# Sheet1.net
KiCad netlist of a schematic drawn in Altium Designer
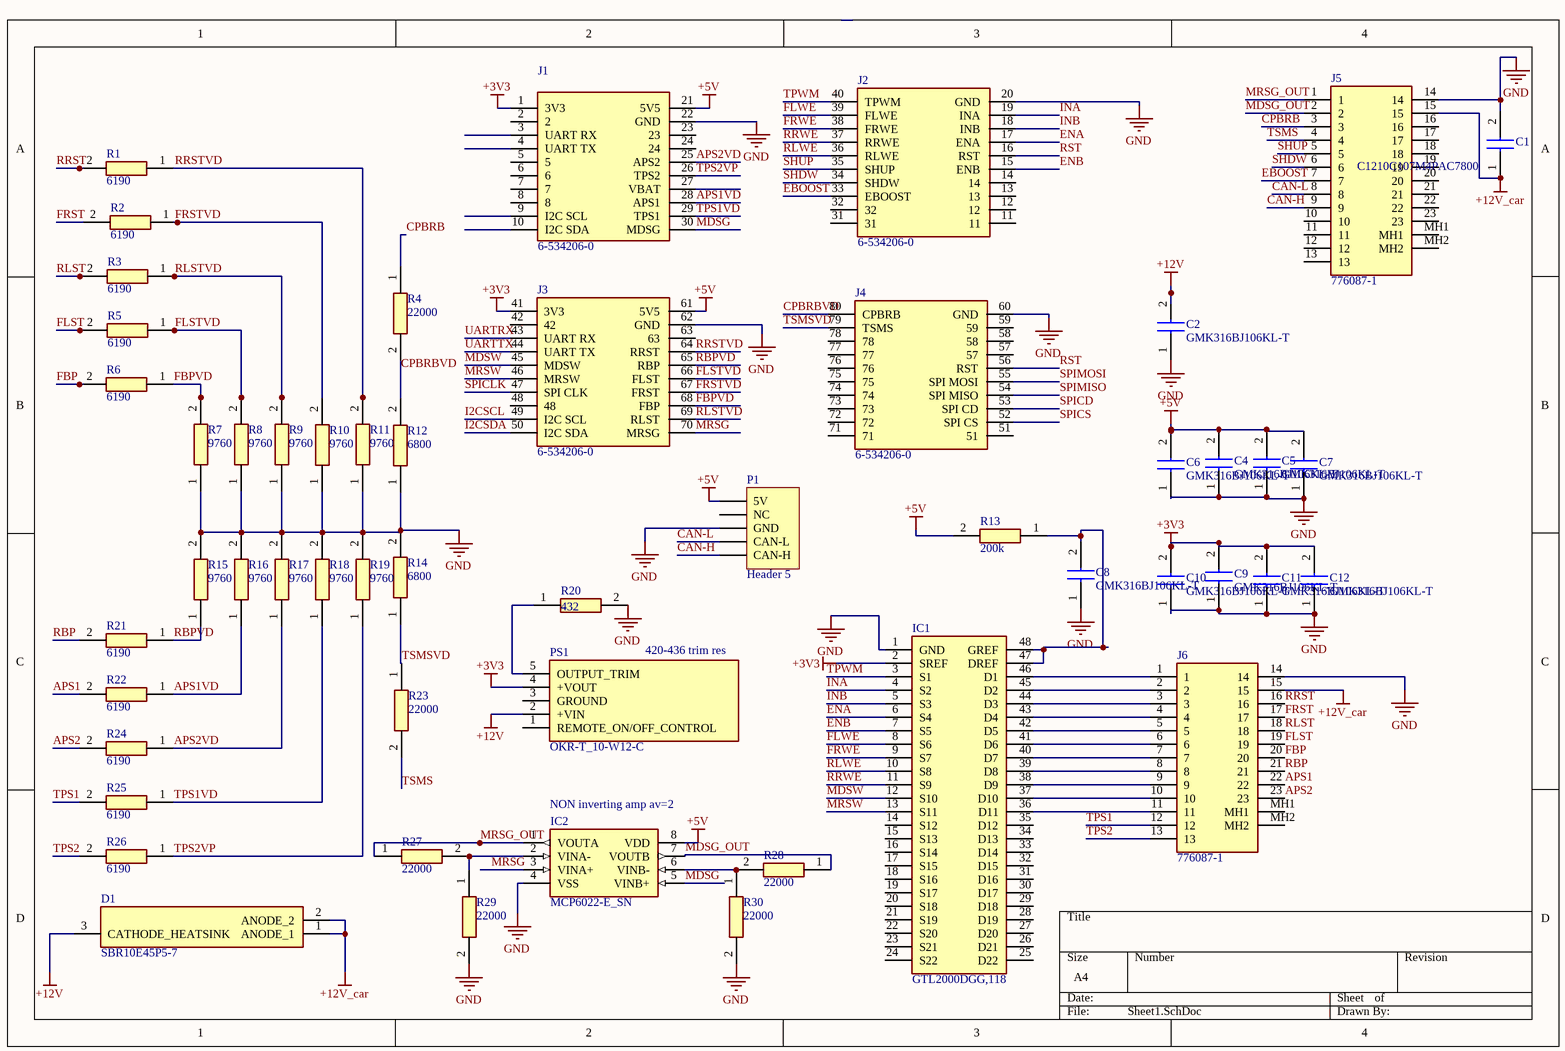
[diagram p0: Sheet1.SchDoc]

(export (version "E")
  (design (tool "Eeschema 10.0.6"))
  (components
    (comp (ref "C1")
      (value "C1210C107M4PAC7800")
      (footprint "SamacSys:CAPC3225X280N")
      (description "Capacitor")
      (libsource (lib "*") (part "C1210C107M4PAC7800"))
    )
    (comp (ref "C2")
      (value "GMK316BJ106KL-T")
      (footprint "SamacSys:CAPC3216X190N")
      (description "Capacitor")
      (fields (field (name "MOUSER PART NUMBER") "963-GMK316BJ106KL-T"))
      (libsource (lib "*") (part "GMK316BJ106KL-T"))
    )
    (comp (ref "C4")
      (value "GMK316BJ106KL-T")
      (footprint "SamacSys:CAPC3216X190N")
      (description "Capacitor")
      (fields (field (name "MOUSER PART NUMBER") "963-GMK316BJ106KL-T"))
      (libsource (lib "*") (part "GMK316BJ106KL-T"))
    )
    (comp (ref "C5")
      (value "GMK316BJ106KL-T")
      (footprint "SamacSys:CAPC3216X190N")
      (description "Capacitor")
      (fields (field (name "MOUSER PART NUMBER") "963-GMK316BJ106KL-T"))
      (libsource (lib "*") (part "GMK316BJ106KL-T"))
    )
    (comp (ref "C6")
      (value "GMK316BJ106KL-T")
      (footprint "SamacSys:CAPC3216X190N")
      (description "Capacitor")
      (fields (field (name "MOUSER PART NUMBER") "963-GMK316BJ106KL-T"))
      (libsource (lib "*") (part "GMK316BJ106KL-T"))
    )
    (comp (ref "C7")
      (value "GMK316BJ106KL-T")
      (footprint "SamacSys:CAPC3216X190N")
      (description "Capacitor")
      (fields (field (name "MOUSER PART NUMBER") "963-GMK316BJ106KL-T"))
      (libsource (lib "*") (part "GMK316BJ106KL-T"))
    )
    (comp (ref "C8")
      (value "GMK316BJ106KL-T")
      (footprint "SamacSys:CAPC3216X190N")
      (description "Capacitor")
      (fields (field (name "MOUSER PART NUMBER") "963-GMK316BJ106KL-T"))
      (libsource (lib "*") (part "GMK316BJ106KL-T"))
    )
    (comp (ref "C9")
      (value "GMK316BJ106KL-T")
      (footprint "SamacSys:CAPC3216X190N")
      (description "Capacitor")
      (fields (field (name "MOUSER PART NUMBER") "963-GMK316BJ106KL-T"))
      (libsource (lib "*") (part "GMK316BJ106KL-T"))
    )
    (comp (ref "C10")
      (value "GMK316BJ106KL-T")
      (footprint "SamacSys:CAPC3216X190N")
      (description "Capacitor")
      (fields (field (name "MOUSER PART NUMBER") "963-GMK316BJ106KL-T"))
      (libsource (lib "*") (part "GMK316BJ106KL-T"))
    )
    (comp (ref "C11")
      (value "GMK316BJ106KL-T")
      (footprint "SamacSys:CAPC3216X190N")
      (description "Capacitor")
      (fields (field (name "MOUSER PART NUMBER") "963-GMK316BJ106KL-T"))
      (libsource (lib "*") (part "GMK316BJ106KL-T"))
    )
    (comp (ref "C12")
      (value "GMK316BJ106KL-T")
      (footprint "SamacSys:CAPC3216X190N")
      (description "Capacitor")
      (fields (field (name "MOUSER PART NUMBER") "963-GMK316BJ106KL-T"))
      (libsource (lib "*") (part "GMK316BJ106KL-T"))
    )
    (comp (ref "D1")
      (value "SBR10E45P5-7")
      (footprint "SamacSys:POWERDI5")
      (description "Schottky Diode")
      (fields (field (name "MOUSER PART NUMBER") "621-SBR10E45P5-7"))
      (libsource (lib "*") (part "SBR10E45P5-7"))
    )
    (comp (ref "IC1")
      (value "GTL2000DGG,118")
      (footprint "SamacSys:SOP50P810X120-48N")
      (description "Integrated Circuit")
      (fields (field (name "MOUSER PART NUMBER") "771-GTL2000DGG118"))
      (libsource (lib "*") (part "GTL2000DGG,118"))
    )
    (comp (ref "IC2")
      (value "MCP6022-E_SN")
      (footprint "SamacSys:SOIC127P600X175-8N")
      (description "Integrated Circuit")
      (fields
        (field (name "MANUFACTURER_PART_NUMBER") "MCP6022-E/SN")
        (field (name "MOUSER PART NUMBER") "579-MCP6022-E/SN")
      )
      (libsource (lib "TiSupervisoryController") (part "MCP6022-E_SN"))
    )
    (comp (ref "J1")
      (value "6-534206-0")
      (footprint "206-0")
      (description "Connector")
      (fields (field (name "MOUSER PART NUMBER") "571-6-534206-0") (field (name "RS PART NUMBER") "6803445P"))
      (libsource (lib "TiSupervisoryController") (part "6-534206-0"))
    )
    (comp (ref "J2")
      (value "6-534206-0")
      (footprint "206-0_1")
      (description "Connector")
      (fields (field (name "MOUSER PART NUMBER") "571-6-534206-0") (field (name "RS PART NUMBER") "6803445P"))
      (libsource (lib "TiSupervisoryController") (part "6-534206-0_1"))
    )
    (comp (ref "J3")
      (value "6-534206-0")
      (footprint "206-0_2")
      (description "Connector")
      (fields (field (name "MOUSER PART NUMBER") "571-6-534206-0") (field (name "RS PART NUMBER") "6803445P"))
      (libsource (lib "TiSupervisoryController") (part "6-534206-0_2"))
    )
    (comp (ref "J4")
      (value "6-534206-0")
      (footprint "206-0_3")
      (description "Connector")
      (fields (field (name "MOUSER PART NUMBER") "571-6-534206-0") (field (name "RS PART NUMBER") "6803445P"))
      (libsource (lib "TiSupervisoryController") (part "6-534206-0_3"))
    )
    (comp (ref "J5")
      (value "776087-1")
      (footprint "PCB1:7760871")
      (description "Connector")
      (fields (field (name "MOUSER PART NUMBER") "571-776087-1") (field (name "RS PART NUMBER") "7181471P"))
      (libsource (lib "*") (part "776087-1"))
    )
    (comp (ref "J6")
      (value "776087-1")
      (footprint "PCB1:7760871")
      (description "Connector")
      (fields (field (name "MOUSER PART NUMBER") "571-776087-1") (field (name "RS PART NUMBER") "7181471P"))
      (libsource (lib "*") (part "776087-1"))
    )
    (comp (ref "P1")
      (value "Header 5")
      (footprint "HDR1X5")
      (description "Header, 5-Pin")
      (fields (field (name "PUBLISHER") "Altium Limited"))
      (libsource (lib "TiSupervisoryController") (part "Header 5"))
    )
    (comp (ref "PS1")
      (value "OKR-T_10-W12-C")
      (footprint "SamacSys:OKRT10W12C")
      (description "Power Supply")
      (fields
        (field (name "MANUFACTURER_PART_NUMBER") "OKR-T/10-W12-C")
        (field (name "MOUSER PART NUMBER") "580-OKR-T/10-W12-C")
      )
      (libsource (lib "*") (part "OKR-T_10-W12-C"))
    )
    (comp (ref "R1")
      (value "6190")
      (footprint "SamacSys:RESC3116X70N")
      (description "Resistor")
      (fields
        (field (name "MANUFACTURER_PART_NUMBER") "ERJ-8ENF6191V")
        (field (name "MOUSER PART NUMBER") "667-ERJ-8ENF6191V")
      )
      (libsource (lib "*") (part "ERJ-8ENF1000V"))
    )
    (comp (ref "R2")
      (value "6190")
      (footprint "SamacSys:RESC3116X70N")
      (description "Resistor")
      (fields
        (field (name "MANUFACTURER_PART_NUMBER") "ERJ-8ENF6191V")
        (field (name "MOUSER PART NUMBER") "667-ERJ-8ENF6191V")
      )
      (libsource (lib "*") (part "ERJ-8ENF1000V"))
    )
    (comp (ref "R3")
      (value "6190")
      (footprint "SamacSys:RESC3116X70N")
      (description "Resistor")
      (fields
        (field (name "MANUFACTURER_PART_NUMBER") "ERJ-8ENF6191V")
        (field (name "MOUSER PART NUMBER") "667-ERJ-8ENF6191V")
      )
      (libsource (lib "*") (part "ERJ-8ENF1000V"))
    )
    (comp (ref "R4")
      (value "22000")
      (footprint "SamacSys:RESC3116X70N")
      (description "Resistor")
      (fields
        (field (name "MANUFACTURER_PART_NUMBER") "ERJ-8ENF2201V")
        (field (name "MOUSER PART NUMBER") "667-ERJ-8ENF2201V")
      )
      (libsource (lib "") (part "ERJ-8ENF1000V_3"))
    )
    (comp (ref "R5")
      (value "6190")
      (footprint "SamacSys:RESC3116X70N")
      (description "Resistor")
      (fields
        (field (name "MANUFACTURER_PART_NUMBER") "ERJ-8ENF6191V")
        (field (name "MOUSER PART NUMBER") "667-ERJ-8ENF6191V")
      )
      (libsource (lib "*") (part "ERJ-8ENF1000V"))
    )
    (comp (ref "R6")
      (value "6190")
      (footprint "SamacSys:RESC3116X70N")
      (description "Resistor")
      (fields
        (field (name "MANUFACTURER_PART_NUMBER") "ERJ-8ENF6191V")
        (field (name "MOUSER PART NUMBER") "667-ERJ-8ENF6191V")
      )
      (libsource (lib "*") (part "ERJ-8ENF1000V"))
    )
    (comp (ref "R7")
      (value "9760")
      (footprint "SamacSys:RESC3116X70N")
      (description "Resistor")
      (fields
        (field (name "MANUFACTURER_PART_NUMBER") "ERJ-8ENF9761V")
        (field (name "MOUSER PART NUMBER") "667-ERJ-8ENF9761V")
      )
      (libsource (lib "") (part "ERJ-8ENF1000V_1"))
    )
    (comp (ref "R8")
      (value "9760")
      (footprint "SamacSys:RESC3116X70N")
      (description "Resistor")
      (fields
        (field (name "MANUFACTURER_PART_NUMBER") "ERJ-8ENF9761V")
        (field (name "MOUSER PART NUMBER") "667-ERJ-8ENF9761V")
      )
      (libsource (lib "") (part "ERJ-8ENF1000V_1"))
    )
    (comp (ref "R9")
      (value "9760")
      (footprint "SamacSys:RESC3116X70N")
      (description "Resistor")
      (fields
        (field (name "MANUFACTURER_PART_NUMBER") "ERJ-8ENF9761V")
        (field (name "MOUSER PART NUMBER") "667-ERJ-8ENF9761V")
      )
      (libsource (lib "") (part "ERJ-8ENF1000V_1"))
    )
    (comp (ref "R10")
      (value "9760")
      (footprint "SamacSys:RESC3116X70N")
      (description "Resistor")
      (fields
        (field (name "MANUFACTURER_PART_NUMBER") "ERJ-8ENF9761V")
        (field (name "MOUSER PART NUMBER") "667-ERJ-8ENF9761V")
      )
      (libsource (lib "") (part "ERJ-8ENF1000V_1"))
    )
    (comp (ref "R11")
      (value "9760")
      (footprint "SamacSys:RESC3116X70N")
      (description "Resistor")
      (fields
        (field (name "MANUFACTURER_PART_NUMBER") "ERJ-8ENF9761V")
        (field (name "MOUSER PART NUMBER") "667-ERJ-8ENF9761V")
      )
      (libsource (lib "") (part "ERJ-8ENF1000V_1"))
    )
    (comp (ref "R12")
      (value "6800")
      (footprint "SamacSys:RESC3116X70N")
      (description "Resistor")
      (fields
        (field (name "MANUFACTURER_PART_NUMBER") "ERJ-8ENF6801V")
        (field (name "MOUSER PART NUMBER") "667-ERJ-8ENF6801V")
      )
      (libsource (lib "") (part "ERJ-8ENF1000V_1"))
    )
    (comp (ref "R13")
      (value "200k")
      (footprint "SamacSys:RESC3116X70N")
      (description "Resistor")
      (fields
        (field (name "MANUFACTURER_PART_NUMBER") "ERJ-8ENF2003V")
        (field (name "MOUSER PART NUMBER") "667-ERJ-8ENF2003V")
      )
      (libsource (lib "*") (part "ERJ-8ENF1000V"))
    )
    (comp (ref "R14")
      (value "6800")
      (footprint "SamacSys:RESC3116X70N")
      (description "Resistor")
      (fields
        (field (name "MANUFACTURER_PART_NUMBER") "ERJ-8ENF6801V")
        (field (name "MOUSER PART NUMBER") "667-ERJ-8ENF6801V")
      )
      (libsource (lib "") (part "ERJ-8ENF1000V_1"))
    )
    (comp (ref "R15")
      (value "9760")
      (footprint "SamacSys:RESC3116X70N")
      (description "Resistor")
      (fields
        (field (name "MANUFACTURER_PART_NUMBER") "ERJ-8ENF9761V")
        (field (name "MOUSER PART NUMBER") "667-ERJ-8ENF9761V")
      )
      (libsource (lib "") (part "ERJ-8ENF1000V_1"))
    )
    (comp (ref "R16")
      (value "9760")
      (footprint "SamacSys:RESC3116X70N")
      (description "Resistor")
      (fields
        (field (name "MANUFACTURER_PART_NUMBER") "ERJ-8ENF9761V")
        (field (name "MOUSER PART NUMBER") "667-ERJ-8ENF9761V")
      )
      (libsource (lib "") (part "ERJ-8ENF1000V_1"))
    )
    (comp (ref "R17")
      (value "9760")
      (footprint "SamacSys:RESC3116X70N")
      (description "Resistor")
      (fields
        (field (name "MANUFACTURER_PART_NUMBER") "ERJ-8ENF9761V")
        (field (name "MOUSER PART NUMBER") "667-ERJ-8ENF9761V")
      )
      (libsource (lib "") (part "ERJ-8ENF1000V_1"))
    )
    (comp (ref "R18")
      (value "9760")
      (footprint "SamacSys:RESC3116X70N")
      (description "Resistor")
      (fields
        (field (name "MANUFACTURER_PART_NUMBER") "ERJ-8ENF9761V")
        (field (name "MOUSER PART NUMBER") "667-ERJ-8ENF9761V")
      )
      (libsource (lib "") (part "ERJ-8ENF1000V_1"))
    )
    (comp (ref "R19")
      (value "9760")
      (footprint "SamacSys:RESC3116X70N")
      (description "Resistor")
      (fields
        (field (name "MANUFACTURER_PART_NUMBER") "ERJ-8ENF9761V")
        (field (name "MOUSER PART NUMBER") "667-ERJ-8ENF9761V")
      )
      (libsource (lib "") (part "ERJ-8ENF1000V_1"))
    )
    (comp (ref "R20")
      (value "432")
      (footprint "SamacSys:RESC3116X70N")
      (description "Resistor")
      (fields
        (field (name "MANUFACTURER_PART_NUMBER") "ERJ-8ENF4320V")
        (field (name "MOUSER PART NUMBER") "667-ERJ-8ENF4320V")
      )
      (libsource (lib "") (part "ERJ-8ENF1000V_2"))
    )
    (comp (ref "R21")
      (value "6190")
      (footprint "SamacSys:RESC3116X70N")
      (description "Resistor")
      (fields
        (field (name "MANUFACTURER_PART_NUMBER") "ERJ-8ENF6191V")
        (field (name "MOUSER PART NUMBER") "667-ERJ-8ENF6191V")
      )
      (libsource (lib "*") (part "ERJ-8ENF1000V"))
    )
    (comp (ref "R22")
      (value "6190")
      (footprint "SamacSys:RESC3116X70N")
      (description "Resistor")
      (fields
        (field (name "MANUFACTURER_PART_NUMBER") "ERJ-8ENF6191V")
        (field (name "MOUSER PART NUMBER") "667-ERJ-8ENF6191V")
      )
      (libsource (lib "*") (part "ERJ-8ENF1000V"))
    )
    (comp (ref "R23")
      (value "22000")
      (footprint "SamacSys:RESC3116X70N")
      (description "Resistor")
      (fields
        (field (name "MANUFACTURER_PART_NUMBER") "ERJ-8ENF2201V")
        (field (name "MOUSER PART NUMBER") "667-ERJ-8ENF2201V")
      )
      (libsource (lib "") (part "ERJ-8ENF1000V_3"))
    )
    (comp (ref "R24")
      (value "6190")
      (footprint "SamacSys:RESC3116X70N")
      (description "Resistor")
      (fields
        (field (name "MANUFACTURER_PART_NUMBER") "ERJ-8ENF6191V")
        (field (name "MOUSER PART NUMBER") "667-ERJ-8ENF6191V")
      )
      (libsource (lib "*") (part "ERJ-8ENF1000V"))
    )
    (comp (ref "R25")
      (value "6190")
      (footprint "SamacSys:RESC3116X70N")
      (description "Resistor")
      (fields
        (field (name "MANUFACTURER_PART_NUMBER") "ERJ-8ENF6191V")
        (field (name "MOUSER PART NUMBER") "667-ERJ-8ENF6191V")
      )
      (libsource (lib "*") (part "ERJ-8ENF1000V"))
    )
    (comp (ref "R26")
      (value "6190")
      (footprint "SamacSys:RESC3116X70N")
      (description "Resistor")
      (fields
        (field (name "MANUFACTURER_PART_NUMBER") "ERJ-8ENF6191V")
        (field (name "MOUSER PART NUMBER") "667-ERJ-8ENF6191V")
      )
      (libsource (lib "*") (part "ERJ-8ENF1000V"))
    )
    (comp (ref "R27")
      (value "22000")
      (footprint "SamacSys:RESC3116X70N")
      (description "Resistor")
      (fields
        (field (name "MANUFACTURER_PART_NUMBER") "ERJ-8ENF2201V")
        (field (name "MOUSER PART NUMBER") "667-ERJ-8ENF2201V")
      )
      (libsource (lib "") (part "ERJ-8ENF1000V_2"))
    )
    (comp (ref "R28")
      (value "22000")
      (footprint "SamacSys:RESC3116X70N")
      (description "Resistor")
      (fields
        (field (name "MANUFACTURER_PART_NUMBER") "ERJ-8ENF2201V")
        (field (name "MOUSER PART NUMBER") "667-ERJ-8ENF2201V")
      )
      (libsource (lib "*") (part "ERJ-8ENF1000V"))
    )
    (comp (ref "R29")
      (value "22000")
      (footprint "SamacSys:RESC3116X70N")
      (description "Resistor")
      (fields
        (field (name "MANUFACTURER_PART_NUMBER") "ERJ-8ENF2201V")
        (field (name "MOUSER PART NUMBER") "667-ERJ-8ENF2201V")
      )
      (libsource (lib "") (part "ERJ-8ENF1000V_3"))
    )
    (comp (ref "R30")
      (value "22000")
      (footprint "SamacSys:RESC3116X70N")
      (description "Resistor")
      (fields
        (field (name "MANUFACTURER_PART_NUMBER") "ERJ-8ENF2201V")
        (field (name "MOUSER PART NUMBER") "667-ERJ-8ENF2201V")
      )
      (libsource (lib "") (part "ERJ-8ENF1000V_3"))
    )
  )
  (nets
    (net (code "1") (name "+3V3") (class "Default")
      (node (ref "C10") (pin "2") (pinfunction "2_2") (pintype "passive"))
      (node (ref "C11") (pin "2") (pinfunction "2_2") (pintype "passive"))
      (node (ref "C12") (pin "2") (pinfunction "2_2") (pintype "passive"))
      (node (ref "C9") (pin "2") (pinfunction "2_2") (pintype "passive"))
      (node (ref "IC1") (pin "2") (pinfunction "SREF_2") (pintype "passive"))
      (node (ref "J1") (pin "1") (pinfunction "3V3_1") (pintype "passive"))
      (node (ref "J3") (pin "41") (pinfunction "3V3_41") (pintype "passive"))
      (node (ref "PS1") (pin "4") (pinfunction "+VOUT_4") (pintype "passive"))
    )
    (net (code "2") (name "+5V") (class "Default")
      (node (ref "C4") (pin "2") (pinfunction "2_2") (pintype "passive"))
      (node (ref "C5") (pin "2") (pinfunction "2_2") (pintype "passive"))
      (node (ref "C6") (pin "2") (pinfunction "2_2") (pintype "passive"))
      (node (ref "C7") (pin "2") (pinfunction "2_2") (pintype "passive"))
      (node (ref "IC2") (pin "8") (pinfunction "VDD_8") (pintype "power_in"))
      (node (ref "J1") (pin "21") (pinfunction "5V5_21") (pintype "passive"))
      (node (ref "J3") (pin "61") (pinfunction "5V5_61") (pintype "passive"))
      (node (ref "P1") (pin "1") (pinfunction "5V_1") (pintype "passive"))
      (node (ref "R13") (pin "2") (pinfunction "2_2") (pintype "passive"))
    )
    (net (code "3") (name "+12V") (class "Default")
      (node (ref "C2") (pin "2") (pinfunction "2_2") (pintype "passive"))
      (node (ref "D1") (pin "3") (pinfunction "CATHODE_HEATSINK_3") (pintype "passive"))
      (node (ref "PS1") (pin "2") (pinfunction "+VIN_2") (pintype "passive"))
    )
    (net (code "4") (name "+12V_car") (class "Default")
      (node (ref "C1") (pin "1") (pinfunction "1_1") (pintype "passive"))
      (node (ref "D1") (pin "1") (pinfunction "ANODE_1_1") (pintype "passive"))
      (node (ref "D1") (pin "2") (pinfunction "ANODE_2_2") (pintype "passive"))
      (node (ref "J5") (pin "15") (pinfunction "15_15") (pintype "passive"))
      (node (ref "J6") (pin "15") (pinfunction "15_15") (pintype "passive"))
    )
    (net (code "5") (name "/APS1") (class "Default")
      (node (ref "J6") (pin "22") (pinfunction "22_22") (pintype "passive"))
      (node (ref "R22") (pin "2") (pinfunction "2_2") (pintype "passive"))
    )
    (net (code "6") (name "/APS1VD") (class "Default")
      (node (ref "J1") (pin "28") (pinfunction "APS1_28") (pintype "passive"))
      (node (ref "R16") (pin "1") (pinfunction "1_1") (pintype "passive"))
      (node (ref "R22") (pin "1") (pinfunction "1_1") (pintype "passive"))
    )
    (net (code "7") (name "/APS2") (class "Default")
      (node (ref "J6") (pin "23") (pinfunction "23_23") (pintype "passive"))
      (node (ref "R24") (pin "2") (pinfunction "2_2") (pintype "passive"))
    )
    (net (code "8") (name "/APS2VD") (class "Default")
      (node (ref "J1") (pin "25") (pinfunction "APS2_25") (pintype "passive"))
      (node (ref "R17") (pin "1") (pinfunction "1_1") (pintype "passive"))
      (node (ref "R24") (pin "1") (pinfunction "1_1") (pintype "passive"))
    )
    (net (code "9") (name "/CAN-H") (class "Default")
      (node (ref "J5") (pin "9") (pinfunction "9_9") (pintype "passive"))
      (node (ref "P1") (pin "5") (pinfunction "CAN-H_5") (pintype "passive"))
    )
    (net (code "10") (name "/CAN-L") (class "Default")
      (node (ref "J5") (pin "8") (pinfunction "8_8") (pintype "passive"))
      (node (ref "P1") (pin "4") (pinfunction "CAN-L_4") (pintype "passive"))
    )
    (net (code "11") (name "/CPBRB") (class "Default")
      (node (ref "J5") (pin "3") (pinfunction "3_3") (pintype "passive"))
      (node (ref "R4") (pin "1") (pinfunction "1_1") (pintype "passive"))
    )
    (net (code "12") (name "/CPBRBVD") (class "Default")
      (node (ref "J4") (pin "80") (pinfunction "CPBRB_80") (pintype "passive"))
      (node (ref "R12") (pin "2") (pinfunction "2_2") (pintype "passive"))
      (node (ref "R4") (pin "2") (pinfunction "2_2") (pintype "passive"))
    )
    (net (code "13") (name "/EBOOST") (class "Default")
      (node (ref "J2") (pin "33") (pinfunction "EBOOST_33") (pintype "passive"))
      (node (ref "J5") (pin "7") (pinfunction "7_7") (pintype "passive"))
    )
    (net (code "14") (name "/ENA") (class "Default")
      (node (ref "IC1") (pin "6") (pinfunction "S4_6") (pintype "passive"))
      (node (ref "J2") (pin "17") (pinfunction "ENA_17") (pintype "passive"))
    )
    (net (code "15") (name "/ENB") (class "Default")
      (node (ref "IC1") (pin "7") (pinfunction "S5_7") (pintype "passive"))
      (node (ref "J2") (pin "15") (pinfunction "ENB_15") (pintype "passive"))
    )
    (net (code "16") (name "/FBP") (class "Default")
      (node (ref "J6") (pin "20") (pinfunction "20_20") (pintype "passive"))
      (node (ref "R6") (pin "2") (pinfunction "2_2") (pintype "passive"))
    )
    (net (code "17") (name "/FBPVD") (class "Default")
      (node (ref "J3") (pin "68") (pinfunction "FBP_68") (pintype "passive"))
      (node (ref "R6") (pin "1") (pinfunction "1_1") (pintype "passive"))
      (node (ref "R7") (pin "2") (pinfunction "2_2") (pintype "passive"))
    )
    (net (code "18") (name "/FLST") (class "Default")
      (node (ref "J6") (pin "19") (pinfunction "19_19") (pintype "passive"))
      (node (ref "R5") (pin "2") (pinfunction "2_2") (pintype "passive"))
    )
    (net (code "19") (name "/FLSTVD") (class "Default")
      (node (ref "J3") (pin "66") (pinfunction "FLST_66") (pintype "passive"))
      (node (ref "R5") (pin "1") (pinfunction "1_1") (pintype "passive"))
      (node (ref "R8") (pin "2") (pinfunction "2_2") (pintype "passive"))
    )
    (net (code "20") (name "/FLWE") (class "Default")
      (node (ref "IC1") (pin "8") (pinfunction "S6_8") (pintype "passive"))
      (node (ref "J2") (pin "39") (pinfunction "FLWE_39") (pintype "passive"))
    )
    (net (code "21") (name "/FRST") (class "Default")
      (node (ref "J6") (pin "17") (pinfunction "17_17") (pintype "passive"))
      (node (ref "R2") (pin "2") (pinfunction "2_2") (pintype "passive"))
    )
    (net (code "22") (name "/FRSTVD") (class "Default")
      (node (ref "J3") (pin "67") (pinfunction "FRST_67") (pintype "passive"))
      (node (ref "R10") (pin "2") (pinfunction "2_2") (pintype "passive"))
      (node (ref "R2") (pin "1") (pinfunction "1_1") (pintype "passive"))
    )
    (net (code "23") (name "/FRWE") (class "Default")
      (node (ref "IC1") (pin "9") (pinfunction "S7_9") (pintype "passive"))
      (node (ref "J2") (pin "38") (pinfunction "FRWE_38") (pintype "passive"))
    )
    (net (code "24") (name "/I2CSCL") (class "Default")
      (node (ref "J3") (pin "49") (pinfunction "I2C_SCL_49") (pintype "passive"))
    )
    (net (code "25") (name "/I2CSDA") (class "Default")
      (node (ref "J3") (pin "50") (pinfunction "I2C_SDA_50") (pintype "passive"))
    )
    (net (code "26") (name "/INA") (class "Default")
      (node (ref "IC1") (pin "4") (pinfunction "S2_4") (pintype "passive"))
      (node (ref "J2") (pin "19") (pinfunction "INA_19") (pintype "passive"))
    )
    (net (code "27") (name "/INB") (class "Default")
      (node (ref "IC1") (pin "5") (pinfunction "S3_5") (pintype "passive"))
      (node (ref "J2") (pin "18") (pinfunction "INB_18") (pintype "passive"))
    )
    (net (code "28") (name "/MDSG") (class "Default")
      (node (ref "IC2") (pin "5") (pinfunction "VINB+_5") (pintype "input"))
      (node (ref "J1") (pin "30") (pinfunction "MDSG_30") (pintype "passive"))
    )
    (net (code "29") (name "/MDSG_OUT") (class "Default")
      (node (ref "IC2") (pin "7") (pinfunction "VOUTB_7") (pintype "output"))
      (node (ref "J5") (pin "2") (pinfunction "2_2") (pintype "passive"))
      (node (ref "R28") (pin "1") (pinfunction "1_1") (pintype "passive"))
    )
    (net (code "30") (name "/MDSW") (class "Default")
      (node (ref "IC1") (pin "12") (pinfunction "S10_12") (pintype "passive"))
      (node (ref "J3") (pin "45") (pinfunction "MDSW_45") (pintype "passive"))
    )
    (net (code "31") (name "/MRSG") (class "Default")
      (node (ref "IC2") (pin "3") (pinfunction "VINA+_3") (pintype "input"))
      (node (ref "J3") (pin "70") (pinfunction "MRSG_70") (pintype "passive"))
    )
    (net (code "32") (name "/MRSG_OUT") (class "Default")
      (node (ref "IC2") (pin "1") (pinfunction "VOUTA_1") (pintype "output"))
      (node (ref "J5") (pin "1") (pinfunction "1_1") (pintype "passive"))
      (node (ref "R27") (pin "1") (pinfunction "1_1") (pintype "passive"))
    )
    (net (code "33") (name "/MRSW") (class "Default")
      (node (ref "IC1") (pin "13") (pinfunction "S11_13") (pintype "passive"))
      (node (ref "J3") (pin "46") (pinfunction "MRSW_46") (pintype "passive"))
    )
    (net (code "34") (name "/RBP") (class "Default")
      (node (ref "J6") (pin "21") (pinfunction "21_21") (pintype "passive"))
      (node (ref "R21") (pin "2") (pinfunction "2_2") (pintype "passive"))
    )
    (net (code "35") (name "/RBPVD") (class "Default")
      (node (ref "J3") (pin "65") (pinfunction "RBP_65") (pintype "passive"))
      (node (ref "R15") (pin "1") (pinfunction "1_1") (pintype "passive"))
      (node (ref "R21") (pin "1") (pinfunction "1_1") (pintype "passive"))
    )
    (net (code "36") (name "/RLST") (class "Default")
      (node (ref "J6") (pin "18") (pinfunction "18_18") (pintype "passive"))
      (node (ref "R3") (pin "2") (pinfunction "2_2") (pintype "passive"))
    )
    (net (code "37") (name "/RLSTVD") (class "Default")
      (node (ref "J3") (pin "69") (pinfunction "RLST_69") (pintype "passive"))
      (node (ref "R3") (pin "1") (pinfunction "1_1") (pintype "passive"))
      (node (ref "R9") (pin "2") (pinfunction "2_2") (pintype "passive"))
    )
    (net (code "38") (name "/RLWE") (class "Default")
      (node (ref "IC1") (pin "10") (pinfunction "S8_10") (pintype "passive"))
      (node (ref "J2") (pin "36") (pinfunction "RLWE_36") (pintype "passive"))
    )
    (net (code "39") (name "/RRST") (class "Default")
      (node (ref "J6") (pin "16") (pinfunction "16_16") (pintype "passive"))
      (node (ref "R1") (pin "2") (pinfunction "2_2") (pintype "passive"))
    )
    (net (code "40") (name "/RRSTVD") (class "Default")
      (node (ref "J3") (pin "64") (pinfunction "RRST_64") (pintype "passive"))
      (node (ref "R1") (pin "1") (pinfunction "1_1") (pintype "passive"))
      (node (ref "R11") (pin "2") (pinfunction "2_2") (pintype "passive"))
    )
    (net (code "41") (name "/RRWE") (class "Default")
      (node (ref "IC1") (pin "11") (pinfunction "S9_11") (pintype "passive"))
      (node (ref "J2") (pin "37") (pinfunction "RRWE_37") (pintype "passive"))
    )
    (net (code "42") (name "/RST") (class "Default")
      (node (ref "J2") (pin "16") (pinfunction "RST_16") (pintype "passive"))
      (node (ref "J4") (pin "56") (pinfunction "RST_56") (pintype "passive"))
    )
    (net (code "43") (name "/SHDW") (class "Default")
      (node (ref "J2") (pin "34") (pinfunction "SHDW_34") (pintype "passive"))
      (node (ref "J5") (pin "6") (pinfunction "6_6") (pintype "passive"))
    )
    (net (code "44") (name "/SHUP") (class "Default")
      (node (ref "J2") (pin "35") (pinfunction "SHUP_35") (pintype "passive"))
      (node (ref "J5") (pin "5") (pinfunction "5_5") (pintype "passive"))
    )
    (net (code "45") (name "/SPICD") (class "Default")
      (node (ref "J4") (pin "53") (pinfunction "SPI_CD_53") (pintype "passive"))
    )
    (net (code "46") (name "/SPICLK") (class "Default")
      (node (ref "J3") (pin "47") (pinfunction "SPI_CLK_47") (pintype "passive"))
    )
    (net (code "47") (name "/SPICS") (class "Default")
      (node (ref "J4") (pin "52") (pinfunction "SPI_CS_52") (pintype "passive"))
    )
    (net (code "48") (name "/SPIMISO") (class "Default")
      (node (ref "J4") (pin "54") (pinfunction "SPI_MISO_54") (pintype "passive"))
    )
    (net (code "49") (name "/SPIMOSI") (class "Default")
      (node (ref "J4") (pin "55") (pinfunction "SPI_MOSI_55") (pintype "passive"))
    )
    (net (code "50") (name "/TPS1") (class "Default")
      (node (ref "J6") (pin "12") (pinfunction "12_12") (pintype "passive"))
      (node (ref "R25") (pin "2") (pinfunction "2_2") (pintype "passive"))
    )
    (net (code "51") (name "/TPS1VD") (class "Default")
      (node (ref "J1") (pin "29") (pinfunction "TPS1_29") (pintype "passive"))
      (node (ref "R18") (pin "1") (pinfunction "1_1") (pintype "passive"))
      (node (ref "R25") (pin "1") (pinfunction "1_1") (pintype "passive"))
    )
    (net (code "52") (name "/TPS2") (class "Default")
      (node (ref "J6") (pin "13") (pinfunction "13_13") (pintype "passive"))
      (node (ref "R26") (pin "2") (pinfunction "2_2") (pintype "passive"))
    )
    (net (code "53") (name "/TPS2VP") (class "Default")
      (node (ref "J1") (pin "26") (pinfunction "TPS2_26") (pintype "passive"))
      (node (ref "R19") (pin "1") (pinfunction "1_1") (pintype "passive"))
      (node (ref "R26") (pin "1") (pinfunction "1_1") (pintype "passive"))
    )
    (net (code "54") (name "/TPWM") (class "Default")
      (node (ref "IC1") (pin "3") (pinfunction "S1_3") (pintype "passive"))
      (node (ref "J2") (pin "40") (pinfunction "TPWM_40") (pintype "passive"))
    )
    (net (code "55") (name "/TSMS") (class "Default")
      (node (ref "J5") (pin "4") (pinfunction "4_4") (pintype "passive"))
      (node (ref "R23") (pin "2") (pinfunction "2_2") (pintype "passive"))
    )
    (net (code "56") (name "/TSMSVD") (class "Default")
      (node (ref "J4") (pin "79") (pinfunction "TSMS_79") (pintype "passive"))
      (node (ref "R14") (pin "1") (pinfunction "1_1") (pintype "passive"))
      (node (ref "R23") (pin "1") (pinfunction "1_1") (pintype "passive"))
    )
    (net (code "57") (name "/UARTRX") (class "Default")
      (node (ref "J3") (pin "43") (pinfunction "UART_RX_43") (pintype "passive"))
    )
    (net (code "58") (name "/UARTTX") (class "Default")
      (node (ref "J3") (pin "44") (pinfunction "UART_TX_44") (pintype "passive"))
    )
    (net (code "59") (name "GND") (class "Default")
      (node (ref "C1") (pin "2") (pinfunction "2_2") (pintype "passive"))
      (node (ref "C10") (pin "1") (pinfunction "1_1") (pintype "passive"))
      (node (ref "C11") (pin "1") (pinfunction "1_1") (pintype "passive"))
      (node (ref "C12") (pin "1") (pinfunction "1_1") (pintype "passive"))
      (node (ref "C2") (pin "1") (pinfunction "1_1") (pintype "passive"))
      (node (ref "C4") (pin "1") (pinfunction "1_1") (pintype "passive"))
      (node (ref "C5") (pin "1") (pinfunction "1_1") (pintype "passive"))
      (node (ref "C6") (pin "1") (pinfunction "1_1") (pintype "passive"))
      (node (ref "C7") (pin "1") (pinfunction "1_1") (pintype "passive"))
      (node (ref "C8") (pin "1") (pinfunction "1_1") (pintype "passive"))
      (node (ref "C9") (pin "1") (pinfunction "1_1") (pintype "passive"))
      (node (ref "IC1") (pin "1") (pinfunction "GND_1") (pintype "passive"))
      (node (ref "IC2") (pin "4") (pinfunction "VSS_4") (pintype "power_in"))
      (node (ref "J1") (pin "22") (pinfunction "GND_22") (pintype "passive"))
      (node (ref "J2") (pin "20") (pinfunction "GND_20") (pintype "passive"))
      (node (ref "J3") (pin "62") (pinfunction "GND_62") (pintype "passive"))
      (node (ref "J4") (pin "60") (pinfunction "GND_60") (pintype "passive"))
      (node (ref "J5") (pin "14") (pinfunction "14_14") (pintype "passive"))
      (node (ref "J6") (pin "14") (pinfunction "14_14") (pintype "passive"))
      (node (ref "P1") (pin "3") (pinfunction "GND_3") (pintype "passive"))
      (node (ref "R10") (pin "1") (pinfunction "1_1") (pintype "passive"))
      (node (ref "R11") (pin "1") (pinfunction "1_1") (pintype "passive"))
      (node (ref "R12") (pin "1") (pinfunction "1_1") (pintype "passive"))
      (node (ref "R14") (pin "2") (pinfunction "2_2") (pintype "passive"))
      (node (ref "R15") (pin "2") (pinfunction "2_2") (pintype "passive"))
      (node (ref "R16") (pin "2") (pinfunction "2_2") (pintype "passive"))
      (node (ref "R17") (pin "2") (pinfunction "2_2") (pintype "passive"))
      (node (ref "R18") (pin "2") (pinfunction "2_2") (pintype "passive"))
      (node (ref "R19") (pin "2") (pinfunction "2_2") (pintype "passive"))
      (node (ref "R20") (pin "2") (pinfunction "2_2") (pintype "passive"))
      (node (ref "R29") (pin "2") (pinfunction "2_2") (pintype "passive"))
      (node (ref "R30") (pin "2") (pinfunction "2_2") (pintype "passive"))
      (node (ref "R7") (pin "1") (pinfunction "1_1") (pintype "passive"))
      (node (ref "R8") (pin "1") (pinfunction "1_1") (pintype "passive"))
      (node (ref "R9") (pin "1") (pinfunction "1_1") (pintype "passive"))
    )
    (net (code "60") (name "Net-(IC1-D1)") (class "Default")
      (node (ref "IC1") (pin "46") (pinfunction "D1_46") (pintype "passive"))
      (node (ref "J6") (pin "1") (pinfunction "1_1") (pintype "passive"))
    )
    (net (code "61") (name "Net-(IC1-D2)") (class "Default")
      (node (ref "IC1") (pin "45") (pinfunction "D2_45") (pintype "passive"))
      (node (ref "J6") (pin "2") (pinfunction "2_2") (pintype "passive"))
    )
    (net (code "62") (name "Net-(IC1-D3)") (class "Default")
      (node (ref "IC1") (pin "44") (pinfunction "D3_44") (pintype "passive"))
      (node (ref "J6") (pin "3") (pinfunction "3_3") (pintype "passive"))
    )
    (net (code "63") (name "Net-(IC1-D4)") (class "Default")
      (node (ref "IC1") (pin "43") (pinfunction "D4_43") (pintype "passive"))
      (node (ref "J6") (pin "4") (pinfunction "4_4") (pintype "passive"))
    )
    (net (code "64") (name "Net-(IC1-D5)") (class "Default")
      (node (ref "IC1") (pin "42") (pinfunction "D5_42") (pintype "passive"))
      (node (ref "J6") (pin "5") (pinfunction "5_5") (pintype "passive"))
    )
    (net (code "65") (name "Net-(IC1-D6)") (class "Default")
      (node (ref "IC1") (pin "41") (pinfunction "D6_41") (pintype "passive"))
      (node (ref "J6") (pin "6") (pinfunction "6_6") (pintype "passive"))
    )
    (net (code "66") (name "Net-(IC1-D7)") (class "Default")
      (node (ref "IC1") (pin "40") (pinfunction "D7_40") (pintype "passive"))
      (node (ref "J6") (pin "7") (pinfunction "7_7") (pintype "passive"))
    )
    (net (code "67") (name "Net-(IC1-D8)") (class "Default")
      (node (ref "IC1") (pin "39") (pinfunction "D8_39") (pintype "passive"))
      (node (ref "J6") (pin "8") (pinfunction "8_8") (pintype "passive"))
    )
    (net (code "68") (name "Net-(IC1-D9)") (class "Default")
      (node (ref "IC1") (pin "38") (pinfunction "D9_38") (pintype "passive"))
      (node (ref "J6") (pin "9") (pinfunction "9_9") (pintype "passive"))
    )
    (net (code "69") (name "Net-(IC1-D10)") (class "Default")
      (node (ref "IC1") (pin "37") (pinfunction "D10_37") (pintype "passive"))
      (node (ref "J6") (pin "10") (pinfunction "10_10") (pintype "passive"))
    )
    (net (code "70") (name "Net-(IC1-D11)") (class "Default")
      (node (ref "IC1") (pin "36") (pinfunction "D11_36") (pintype "passive"))
      (node (ref "J6") (pin "11") (pinfunction "11_11") (pintype "passive"))
    )
    (net (code "71") (name "Net-(IC1-DREF)") (class "Default")
      (node (ref "C8") (pin "2") (pinfunction "2_2") (pintype "passive"))
      (node (ref "IC1") (pin "47") (pinfunction "DREF_47") (pintype "passive"))
      (node (ref "IC1") (pin "48") (pinfunction "GREF_48") (pintype "passive"))
      (node (ref "R13") (pin "1") (pinfunction "1_1") (pintype "passive"))
    )
    (net (code "72") (name "Net-(IC2-VINA-)") (class "Default")
      (node (ref "IC2") (pin "2") (pinfunction "VINA-_2") (pintype "input"))
      (node (ref "R27") (pin "2") (pinfunction "2_2") (pintype "passive"))
      (node (ref "R29") (pin "1") (pinfunction "1_1") (pintype "passive"))
    )
    (net (code "73") (name "Net-(IC2-VINB-)") (class "Default")
      (node (ref "IC2") (pin "6") (pinfunction "VINB-_6") (pintype "input"))
      (node (ref "R28") (pin "2") (pinfunction "2_2") (pintype "passive"))
      (node (ref "R30") (pin "1") (pinfunction "1_1") (pintype "passive"))
    )
    (net (code "74") (name "Net-(PS1-OUTPUT_TRIM)") (class "Default")
      (node (ref "PS1") (pin "5") (pinfunction "OUTPUT_TRIM_5") (pintype "passive"))
      (node (ref "R20") (pin "1") (pinfunction "1_1") (pintype "passive"))
    )
    (net (code "75") (name "unconnected-(IC1-D12-Pad35)") (class "Default")
      (node (ref "IC1") (pin "35") (pinfunction "D12_35") (pintype "passive"))
    )
    (net (code "76") (name "unconnected-(IC1-D13-Pad34)") (class "Default")
      (node (ref "IC1") (pin "34") (pinfunction "D13_34") (pintype "passive"))
    )
    (net (code "77") (name "unconnected-(IC1-D14-Pad33)") (class "Default")
      (node (ref "IC1") (pin "33") (pinfunction "D14_33") (pintype "passive"))
    )
    (net (code "78") (name "unconnected-(IC1-D15-Pad32)") (class "Default")
      (node (ref "IC1") (pin "32") (pinfunction "D15_32") (pintype "passive"))
    )
    (net (code "79") (name "unconnected-(IC1-D16-Pad31)") (class "Default")
      (node (ref "IC1") (pin "31") (pinfunction "D16_31") (pintype "passive"))
    )
    (net (code "80") (name "unconnected-(IC1-D17-Pad30)") (class "Default")
      (node (ref "IC1") (pin "30") (pinfunction "D17_30") (pintype "passive"))
    )
    (net (code "81") (name "unconnected-(IC1-D18-Pad29)") (class "Default")
      (node (ref "IC1") (pin "29") (pinfunction "D18_29") (pintype "passive"))
    )
    (net (code "82") (name "unconnected-(IC1-D19-Pad28)") (class "Default")
      (node (ref "IC1") (pin "28") (pinfunction "D19_28") (pintype "passive"))
    )
    (net (code "83") (name "unconnected-(IC1-D20-Pad27)") (class "Default")
      (node (ref "IC1") (pin "27") (pinfunction "D20_27") (pintype "passive"))
    )
    (net (code "84") (name "unconnected-(IC1-D21-Pad26)") (class "Default")
      (node (ref "IC1") (pin "26") (pinfunction "D21_26") (pintype "passive"))
    )
    (net (code "85") (name "unconnected-(IC1-D22-Pad25)") (class "Default")
      (node (ref "IC1") (pin "25") (pinfunction "D22_25") (pintype "passive"))
    )
    (net (code "86") (name "unconnected-(IC1-S12-Pad14)") (class "Default")
      (node (ref "IC1") (pin "14") (pinfunction "S12_14") (pintype "passive"))
    )
    (net (code "87") (name "unconnected-(IC1-S13-Pad15)") (class "Default")
      (node (ref "IC1") (pin "15") (pinfunction "S13_15") (pintype "passive"))
    )
    (net (code "88") (name "unconnected-(IC1-S14-Pad16)") (class "Default")
      (node (ref "IC1") (pin "16") (pinfunction "S14_16") (pintype "passive"))
    )
    (net (code "89") (name "unconnected-(IC1-S15-Pad17)") (class "Default")
      (node (ref "IC1") (pin "17") (pinfunction "S15_17") (pintype "passive"))
    )
    (net (code "90") (name "unconnected-(IC1-S16-Pad18)") (class "Default")
      (node (ref "IC1") (pin "18") (pinfunction "S16_18") (pintype "passive"))
    )
    (net (code "91") (name "unconnected-(IC1-S17-Pad19)") (class "Default")
      (node (ref "IC1") (pin "19") (pinfunction "S17_19") (pintype "passive"))
    )
    (net (code "92") (name "unconnected-(IC1-S18-Pad20)") (class "Default")
      (node (ref "IC1") (pin "20") (pinfunction "S18_20") (pintype "passive"))
    )
    (net (code "93") (name "unconnected-(IC1-S19-Pad21)") (class "Default")
      (node (ref "IC1") (pin "21") (pinfunction "S19_21") (pintype "passive"))
    )
    (net (code "94") (name "unconnected-(IC1-S20-Pad22)") (class "Default")
      (node (ref "IC1") (pin "22") (pinfunction "S20_22") (pintype "passive"))
    )
    (net (code "95") (name "unconnected-(IC1-S21-Pad23)") (class "Default")
      (node (ref "IC1") (pin "23") (pinfunction "S21_23") (pintype "passive"))
    )
    (net (code "96") (name "unconnected-(IC1-S22-Pad24)") (class "Default")
      (node (ref "IC1") (pin "24") (pinfunction "S22_24") (pintype "passive"))
    )
    (net (code "97") (name "unconnected-(J1-I2C_SCL-Pad9)") (class "Default")
      (node (ref "J1") (pin "9") (pinfunction "I2C_SCL_9") (pintype "passive"))
    )
    (net (code "98") (name "unconnected-(J1-I2C_SDA-Pad10)") (class "Default")
      (node (ref "J1") (pin "10") (pinfunction "I2C_SDA_10") (pintype "passive"))
    )
    (net (code "99") (name "unconnected-(J1-Pad2)") (class "Default")
      (node (ref "J1") (pin "2") (pinfunction "2_2") (pintype "passive"))
    )
    (net (code "100") (name "unconnected-(J1-Pad5)") (class "Default")
      (node (ref "J1") (pin "5") (pinfunction "5_5") (pintype "passive"))
    )
    (net (code "101") (name "unconnected-(J1-Pad6)") (class "Default")
      (node (ref "J1") (pin "6") (pinfunction "6_6") (pintype "passive"))
    )
    (net (code "102") (name "unconnected-(J1-Pad7)") (class "Default")
      (node (ref "J1") (pin "7") (pinfunction "7_7") (pintype "passive"))
    )
    (net (code "103") (name "unconnected-(J1-Pad8)") (class "Default")
      (node (ref "J1") (pin "8") (pinfunction "8_8") (pintype "passive"))
    )
    (net (code "104") (name "unconnected-(J1-Pad23)") (class "Default")
      (node (ref "J1") (pin "23") (pinfunction "23_23") (pintype "passive"))
    )
    (net (code "105") (name "unconnected-(J1-Pad24)") (class "Default")
      (node (ref "J1") (pin "24") (pinfunction "24_24") (pintype "passive"))
    )
    (net (code "106") (name "unconnected-(J1-UART_RX-Pad3)") (class "Default")
      (node (ref "J1") (pin "3") (pinfunction "UART_RX_3") (pintype "passive"))
    )
    (net (code "107") (name "unconnected-(J1-UART_TX-Pad4)") (class "Default")
      (node (ref "J1") (pin "4") (pinfunction "UART_TX_4") (pintype "passive"))
    )
    (net (code "108") (name "unconnected-(J1-VBAT-Pad27)") (class "Default")
      (node (ref "J1") (pin "27") (pinfunction "VBAT_27") (pintype "passive"))
    )
    (net (code "109") (name "unconnected-(J2-Pad11)") (class "Default")
      (node (ref "J2") (pin "11") (pinfunction "11_11") (pintype "passive"))
    )
    (net (code "110") (name "unconnected-(J2-Pad12)") (class "Default")
      (node (ref "J2") (pin "12") (pinfunction "12_12") (pintype "passive"))
    )
    (net (code "111") (name "unconnected-(J2-Pad13)") (class "Default")
      (node (ref "J2") (pin "13") (pinfunction "13_13") (pintype "passive"))
    )
    (net (code "112") (name "unconnected-(J2-Pad14)") (class "Default")
      (node (ref "J2") (pin "14") (pinfunction "14_14") (pintype "passive"))
    )
    (net (code "113") (name "unconnected-(J2-Pad31)") (class "Default")
      (node (ref "J2") (pin "31") (pinfunction "31_31") (pintype "passive"))
    )
    (net (code "114") (name "unconnected-(J2-Pad32)") (class "Default")
      (node (ref "J2") (pin "32") (pinfunction "32_32") (pintype "passive"))
    )
    (net (code "115") (name "unconnected-(J3-Pad42)") (class "Default")
      (node (ref "J3") (pin "42") (pinfunction "42_42") (pintype "passive"))
    )
    (net (code "116") (name "unconnected-(J3-Pad48)") (class "Default")
      (node (ref "J3") (pin "48") (pinfunction "48_48") (pintype "passive"))
    )
    (net (code "117") (name "unconnected-(J3-Pad63)") (class "Default")
      (node (ref "J3") (pin "63") (pinfunction "63_63") (pintype "passive"))
    )
    (net (code "118") (name "unconnected-(J4-Pad51)") (class "Default")
      (node (ref "J4") (pin "51") (pinfunction "51_51") (pintype "passive"))
    )
    (net (code "119") (name "unconnected-(J4-Pad57)") (class "Default")
      (node (ref "J4") (pin "57") (pinfunction "57_57") (pintype "passive"))
    )
    (net (code "120") (name "unconnected-(J4-Pad58)") (class "Default")
      (node (ref "J4") (pin "58") (pinfunction "58_58") (pintype "passive"))
    )
    (net (code "121") (name "unconnected-(J4-Pad59)") (class "Default")
      (node (ref "J4") (pin "59") (pinfunction "59_59") (pintype "passive"))
    )
    (net (code "122") (name "unconnected-(J4-Pad71)") (class "Default")
      (node (ref "J4") (pin "71") (pinfunction "71_71") (pintype "passive"))
    )
    (net (code "123") (name "unconnected-(J4-Pad72)") (class "Default")
      (node (ref "J4") (pin "72") (pinfunction "72_72") (pintype "passive"))
    )
    (net (code "124") (name "unconnected-(J4-Pad73)") (class "Default")
      (node (ref "J4") (pin "73") (pinfunction "73_73") (pintype "passive"))
    )
    (net (code "125") (name "unconnected-(J4-Pad74)") (class "Default")
      (node (ref "J4") (pin "74") (pinfunction "74_74") (pintype "passive"))
    )
    (net (code "126") (name "unconnected-(J4-Pad75)") (class "Default")
      (node (ref "J4") (pin "75") (pinfunction "75_75") (pintype "passive"))
    )
    (net (code "127") (name "unconnected-(J4-Pad76)") (class "Default")
      (node (ref "J4") (pin "76") (pinfunction "76_76") (pintype "passive"))
    )
    (net (code "128") (name "unconnected-(J4-Pad77)") (class "Default")
      (node (ref "J4") (pin "77") (pinfunction "77_77") (pintype "passive"))
    )
    (net (code "129") (name "unconnected-(J4-Pad78)") (class "Default")
      (node (ref "J4") (pin "78") (pinfunction "78_78") (pintype "passive"))
    )
    (net (code "130") (name "unconnected-(J5-Pad10)") (class "Default")
      (node (ref "J5") (pin "10") (pinfunction "10_10") (pintype "passive"))
    )
    (net (code "131") (name "unconnected-(J5-Pad11)") (class "Default")
      (node (ref "J5") (pin "11") (pinfunction "11_11") (pintype "passive"))
    )
    (net (code "132") (name "unconnected-(J5-Pad12)") (class "Default")
      (node (ref "J5") (pin "12") (pinfunction "12_12") (pintype "passive"))
    )
    (net (code "133") (name "unconnected-(J5-Pad13)") (class "Default")
      (node (ref "J5") (pin "13") (pinfunction "13_13") (pintype "passive"))
    )
    (net (code "134") (name "unconnected-(J5-Pad16)") (class "Default")
      (node (ref "J5") (pin "16") (pinfunction "16_16") (pintype "passive"))
    )
    (net (code "135") (name "unconnected-(J5-Pad17)") (class "Default")
      (node (ref "J5") (pin "17") (pinfunction "17_17") (pintype "passive"))
    )
    (net (code "136") (name "unconnected-(J5-Pad18)") (class "Default")
      (node (ref "J5") (pin "18") (pinfunction "18_18") (pintype "passive"))
    )
    (net (code "137") (name "unconnected-(J5-Pad19)") (class "Default")
      (node (ref "J5") (pin "19") (pinfunction "19_19") (pintype "passive"))
    )
    (net (code "138") (name "unconnected-(J5-Pad20)") (class "Default")
      (node (ref "J5") (pin "20") (pinfunction "20_20") (pintype "passive"))
    )
    (net (code "139") (name "unconnected-(J5-Pad21)") (class "Default")
      (node (ref "J5") (pin "21") (pinfunction "21_21") (pintype "passive"))
    )
    (net (code "140") (name "unconnected-(J5-Pad22)") (class "Default")
      (node (ref "J5") (pin "22") (pinfunction "22_22") (pintype "passive"))
    )
    (net (code "141") (name "unconnected-(J5-Pad23)") (class "Default")
      (node (ref "J5") (pin "23") (pinfunction "23_23") (pintype "passive"))
    )
    (net (code "142") (name "unconnected-(J5-PadMH1)") (class "Default")
      (node (ref "J5") (pin "MH1") (pinfunction "MH1_MH1") (pintype "passive"))
    )
    (net (code "143") (name "unconnected-(J5-PadMH2)") (class "Default")
      (node (ref "J5") (pin "MH2") (pinfunction "MH2_MH2") (pintype "passive"))
    )
    (net (code "144") (name "unconnected-(J6-PadMH1)") (class "Default")
      (node (ref "J6") (pin "MH1") (pinfunction "MH1_MH1") (pintype "passive"))
    )
    (net (code "145") (name "unconnected-(J6-PadMH2)") (class "Default")
      (node (ref "J6") (pin "MH2") (pinfunction "MH2_MH2") (pintype "passive"))
    )
    (net (code "146") (name "unconnected-(P1-NC-Pad2)") (class "Default")
      (node (ref "P1") (pin "2") (pinfunction "NC_2") (pintype "passive"))
    )
    (net (code "147") (name "unconnected-(PS1-GROUND-Pad3)") (class "Default")
      (node (ref "PS1") (pin "3") (pinfunction "GROUND_3") (pintype "passive"))
    )
    (net (code "148") (name "unconnected-(PS1-REMOTE_ON{slash}OFF_CONTROL-Pad1)") (class "Default")
      (node (ref "PS1") (pin "1") (pinfunction "REMOTE_ON/OFF_CONTROL_1") (pintype "passive"))
    )
  )
)
